# sch_LEDCUBE.net
KiCad netlist of a schematic drawn in Altium Designer
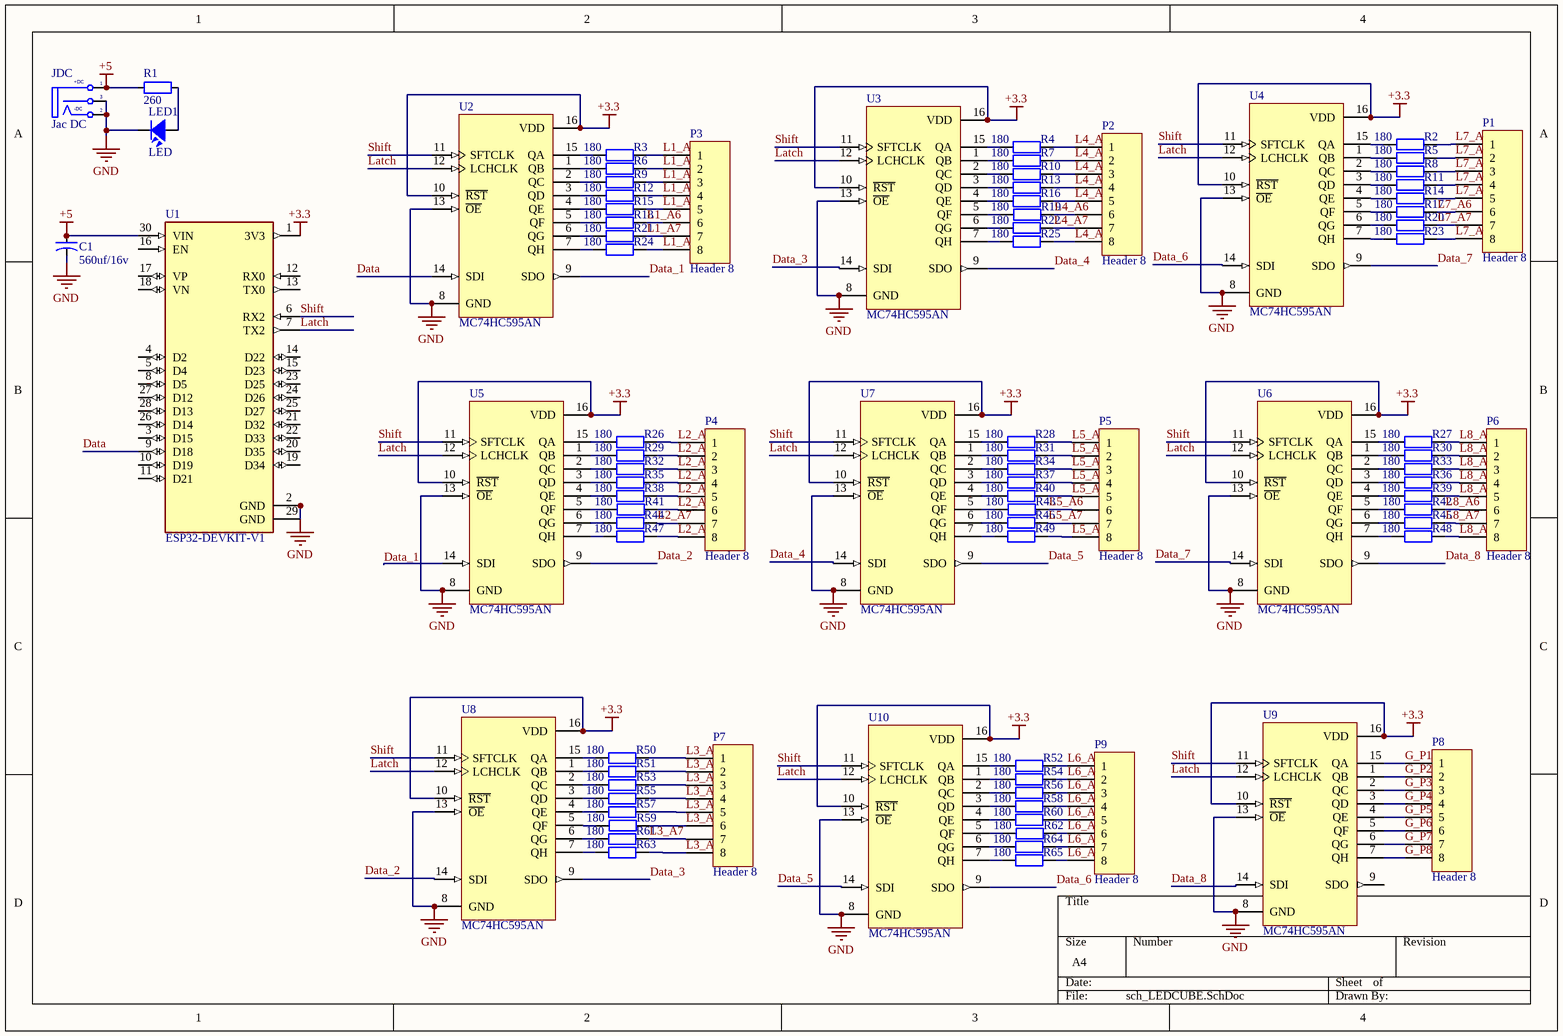
[diagram p0: sch_LEDCUBE.SchDoc]

(export (version "E")
  (design (tool "Eeschema 10.0.6"))
  (components
    (comp (ref "C1")
      (value "560uf/16v")
      (footprint "CA-ALU-8")
      (description "Capacitor (Semiconductor SIM Model)")
      (libsource (lib "My Library") (part "CAP-ALU-DIP"))
    )
    (comp (ref "JDC")
      (value "Jac DC")
      (footprint "DC-IN")
      (description "Jac DC input")
      (libsource (lib "My Library") (part "DCIN"))
    )
    (comp (ref "LED1")
      (value "LED")
      (footprint "LED-3")
      (description "LED Single colour Green and Red")
      (libsource (lib "My Library") (part "LED"))
    )
    (comp (ref "P1")
      (value "Header 8")
      (footprint "CON_8P")
      (description "Header, 8-Pin")
      (libsource (lib "My Library") (part "Header 8"))
    )
    (comp (ref "P2")
      (value "Header 8")
      (footprint "CON_8P")
      (description "Header, 8-Pin")
      (libsource (lib "My Library") (part "Header 8"))
    )
    (comp (ref "P3")
      (value "Header 8")
      (footprint "CON_8P")
      (description "Header, 8-Pin")
      (libsource (lib "My Library") (part "Header 8"))
    )
    (comp (ref "P4")
      (value "Header 8")
      (footprint "CON_8P")
      (description "Header, 8-Pin")
      (libsource (lib "My Library") (part "Header 8"))
    )
    (comp (ref "P5")
      (value "Header 8")
      (footprint "CON_8P")
      (description "Header, 8-Pin")
      (libsource (lib "My Library") (part "Header 8"))
    )
    (comp (ref "P6")
      (value "Header 8")
      (footprint "CON_8P")
      (description "Header, 8-Pin")
      (libsource (lib "My Library") (part "Header 8"))
    )
    (comp (ref "P7")
      (value "Header 8")
      (footprint "CON_8P")
      (description "Header, 8-Pin")
      (libsource (lib "My Library") (part "Header 8"))
    )
    (comp (ref "P8")
      (value "Header 8")
      (footprint "CON_8P")
      (description "Header, 8-Pin")
      (libsource (lib "My Library") (part "Header 8"))
    )
    (comp (ref "P9")
      (value "Header 8")
      (footprint "CON_8P")
      (description "Header, 8-Pin")
      (libsource (lib "My Library") (part "Header 8"))
    )
    (comp (ref "R1")
      (value "260")
      (footprint "RES-1/8W")
      (description "Resistor - DIP")
      (libsource (lib "My Library") (part "Resistor - DIP"))
    )
    (comp (ref "R2")
      (value "180")
      (footprint "RES-SMD-1206")
      (description "Resistor SMD")
      (fields (field (name "MANUFACTURER") "Generic Components"))
      (libsource (lib "My Library") (part "Resistor - SMD"))
    )
    (comp (ref "R3")
      (value "180")
      (footprint "RES-SMD-1206")
      (description "Resistor SMD")
      (fields (field (name "MANUFACTURER") "Generic Components"))
      (libsource (lib "My Library") (part "Resistor - SMD"))
    )
    (comp (ref "R4")
      (value "180")
      (footprint "RES-SMD-1206")
      (description "Resistor SMD")
      (fields (field (name "MANUFACTURER") "Generic Components"))
      (libsource (lib "My Library") (part "Resistor - SMD"))
    )
    (comp (ref "R5")
      (value "180")
      (footprint "RES-SMD-1206")
      (description "Resistor SMD")
      (fields (field (name "MANUFACTURER") "Generic Components"))
      (libsource (lib "My Library") (part "Resistor - SMD"))
    )
    (comp (ref "R6")
      (value "180")
      (footprint "RES-SMD-1206")
      (description "Resistor SMD")
      (fields (field (name "MANUFACTURER") "Generic Components"))
      (libsource (lib "My Library") (part "Resistor - SMD"))
    )
    (comp (ref "R7")
      (value "180")
      (footprint "RES-SMD-1206")
      (description "Resistor SMD")
      (fields (field (name "MANUFACTURER") "Generic Components"))
      (libsource (lib "My Library") (part "Resistor - SMD"))
    )
    (comp (ref "R8")
      (value "180")
      (footprint "RES-SMD-1206")
      (description "Resistor SMD")
      (fields (field (name "MANUFACTURER") "Generic Components"))
      (libsource (lib "My Library") (part "Resistor - SMD"))
    )
    (comp (ref "R9")
      (value "180")
      (footprint "RES-SMD-1206")
      (description "Resistor SMD")
      (fields (field (name "MANUFACTURER") "Generic Components"))
      (libsource (lib "My Library") (part "Resistor - SMD"))
    )
    (comp (ref "R10")
      (value "180")
      (footprint "RES-SMD-1206")
      (description "Resistor SMD")
      (fields (field (name "MANUFACTURER") "Generic Components"))
      (libsource (lib "My Library") (part "Resistor - SMD"))
    )
    (comp (ref "R11")
      (value "180")
      (footprint "RES-SMD-1206")
      (description "Resistor SMD")
      (fields (field (name "MANUFACTURER") "Generic Components"))
      (libsource (lib "My Library") (part "Resistor - SMD"))
    )
    (comp (ref "R12")
      (value "180")
      (footprint "RES-SMD-1206")
      (description "Resistor SMD")
      (fields (field (name "MANUFACTURER") "Generic Components"))
      (libsource (lib "My Library") (part "Resistor - SMD"))
    )
    (comp (ref "R13")
      (value "180")
      (footprint "RES-SMD-1206")
      (description "Resistor SMD")
      (fields (field (name "MANUFACTURER") "Generic Components"))
      (libsource (lib "My Library") (part "Resistor - SMD"))
    )
    (comp (ref "R14")
      (value "180")
      (footprint "RES-SMD-1206")
      (description "Resistor SMD")
      (fields (field (name "MANUFACTURER") "Generic Components"))
      (libsource (lib "My Library") (part "Resistor - SMD"))
    )
    (comp (ref "R15")
      (value "180")
      (footprint "RES-SMD-1206")
      (description "Resistor SMD")
      (fields (field (name "MANUFACTURER") "Generic Components"))
      (libsource (lib "My Library") (part "Resistor - SMD"))
    )
    (comp (ref "R16")
      (value "180")
      (footprint "RES-SMD-1206")
      (description "Resistor SMD")
      (fields (field (name "MANUFACTURER") "Generic Components"))
      (libsource (lib "My Library") (part "Resistor - SMD"))
    )
    (comp (ref "R17")
      (value "180")
      (footprint "RES-SMD-1206")
      (description "Resistor SMD")
      (fields (field (name "MANUFACTURER") "Generic Components"))
      (libsource (lib "My Library") (part "Resistor - SMD"))
    )
    (comp (ref "R18")
      (value "180")
      (footprint "RES-SMD-1206")
      (description "Resistor SMD")
      (fields (field (name "MANUFACTURER") "Generic Components"))
      (libsource (lib "My Library") (part "Resistor - SMD"))
    )
    (comp (ref "R19")
      (value "180")
      (footprint "RES-SMD-1206")
      (description "Resistor SMD")
      (fields (field (name "MANUFACTURER") "Generic Components"))
      (libsource (lib "My Library") (part "Resistor - SMD"))
    )
    (comp (ref "R20")
      (value "180")
      (footprint "RES-SMD-1206")
      (description "Resistor SMD")
      (fields (field (name "MANUFACTURER") "Generic Components"))
      (libsource (lib "My Library") (part "Resistor - SMD"))
    )
    (comp (ref "R21")
      (value "180")
      (footprint "RES-SMD-1206")
      (description "Resistor SMD")
      (fields (field (name "MANUFACTURER") "Generic Components"))
      (libsource (lib "My Library") (part "Resistor - SMD"))
    )
    (comp (ref "R22")
      (value "180")
      (footprint "RES-SMD-1206")
      (description "Resistor SMD")
      (fields (field (name "MANUFACTURER") "Generic Components"))
      (libsource (lib "My Library") (part "Resistor - SMD"))
    )
    (comp (ref "R23")
      (value "180")
      (footprint "RES-SMD-1206")
      (description "Resistor SMD")
      (fields (field (name "MANUFACTURER") "Generic Components"))
      (libsource (lib "My Library") (part "Resistor - SMD"))
    )
    (comp (ref "R24")
      (value "180")
      (footprint "RES-SMD-1206")
      (description "Resistor SMD")
      (fields (field (name "MANUFACTURER") "Generic Components"))
      (libsource (lib "My Library") (part "Resistor - SMD"))
    )
    (comp (ref "R25")
      (value "180")
      (footprint "RES-SMD-1206")
      (description "Resistor SMD")
      (fields (field (name "MANUFACTURER") "Generic Components"))
      (libsource (lib "My Library") (part "Resistor - SMD"))
    )
    (comp (ref "R26")
      (value "180")
      (footprint "RES-SMD-1206")
      (description "Resistor SMD")
      (fields (field (name "MANUFACTURER") "Generic Components"))
      (libsource (lib "My Library") (part "Resistor - SMD"))
    )
    (comp (ref "R27")
      (value "180")
      (footprint "RES-SMD-1206")
      (description "Resistor SMD")
      (fields (field (name "MANUFACTURER") "Generic Components"))
      (libsource (lib "My Library") (part "Resistor - SMD"))
    )
    (comp (ref "R28")
      (value "180")
      (footprint "RES-SMD-1206")
      (description "Resistor SMD")
      (fields (field (name "MANUFACTURER") "Generic Components"))
      (libsource (lib "My Library") (part "Resistor - SMD"))
    )
    (comp (ref "R29")
      (value "180")
      (footprint "RES-SMD-1206")
      (description "Resistor SMD")
      (fields (field (name "MANUFACTURER") "Generic Components"))
      (libsource (lib "My Library") (part "Resistor - SMD"))
    )
    (comp (ref "R30")
      (value "180")
      (footprint "RES-SMD-1206")
      (description "Resistor SMD")
      (fields (field (name "MANUFACTURER") "Generic Components"))
      (libsource (lib "My Library") (part "Resistor - SMD"))
    )
    (comp (ref "R31")
      (value "180")
      (footprint "RES-SMD-1206")
      (description "Resistor SMD")
      (fields (field (name "MANUFACTURER") "Generic Components"))
      (libsource (lib "My Library") (part "Resistor - SMD"))
    )
    (comp (ref "R32")
      (value "180")
      (footprint "RES-SMD-1206")
      (description "Resistor SMD")
      (fields (field (name "MANUFACTURER") "Generic Components"))
      (libsource (lib "My Library") (part "Resistor - SMD"))
    )
    (comp (ref "R33")
      (value "180")
      (footprint "RES-SMD-1206")
      (description "Resistor SMD")
      (fields (field (name "MANUFACTURER") "Generic Components"))
      (libsource (lib "My Library") (part "Resistor - SMD"))
    )
    (comp (ref "R34")
      (value "180")
      (footprint "RES-SMD-1206")
      (description "Resistor SMD")
      (fields (field (name "MANUFACTURER") "Generic Components"))
      (libsource (lib "My Library") (part "Resistor - SMD"))
    )
    (comp (ref "R35")
      (value "180")
      (footprint "RES-SMD-1206")
      (description "Resistor SMD")
      (fields (field (name "MANUFACTURER") "Generic Components"))
      (libsource (lib "My Library") (part "Resistor - SMD"))
    )
    (comp (ref "R36")
      (value "180")
      (footprint "RES-SMD-1206")
      (description "Resistor SMD")
      (fields (field (name "MANUFACTURER") "Generic Components"))
      (libsource (lib "My Library") (part "Resistor - SMD"))
    )
    (comp (ref "R37")
      (value "180")
      (footprint "RES-SMD-1206")
      (description "Resistor SMD")
      (fields (field (name "MANUFACTURER") "Generic Components"))
      (libsource (lib "My Library") (part "Resistor - SMD"))
    )
    (comp (ref "R38")
      (value "180")
      (footprint "RES-SMD-1206")
      (description "Resistor SMD")
      (fields (field (name "MANUFACTURER") "Generic Components"))
      (libsource (lib "My Library") (part "Resistor - SMD"))
    )
    (comp (ref "R39")
      (value "180")
      (footprint "RES-SMD-1206")
      (description "Resistor SMD")
      (fields (field (name "MANUFACTURER") "Generic Components"))
      (libsource (lib "My Library") (part "Resistor - SMD"))
    )
    (comp (ref "R40")
      (value "180")
      (footprint "RES-SMD-1206")
      (description "Resistor SMD")
      (fields (field (name "MANUFACTURER") "Generic Components"))
      (libsource (lib "My Library") (part "Resistor - SMD"))
    )
    (comp (ref "R41")
      (value "180")
      (footprint "RES-SMD-1206")
      (description "Resistor SMD")
      (fields (field (name "MANUFACTURER") "Generic Components"))
      (libsource (lib "My Library") (part "Resistor - SMD"))
    )
    (comp (ref "R42")
      (value "180")
      (footprint "RES-SMD-1206")
      (description "Resistor SMD")
      (fields (field (name "MANUFACTURER") "Generic Components"))
      (libsource (lib "My Library") (part "Resistor - SMD"))
    )
    (comp (ref "R43")
      (value "180")
      (footprint "RES-SMD-1206")
      (description "Resistor SMD")
      (fields (field (name "MANUFACTURER") "Generic Components"))
      (libsource (lib "My Library") (part "Resistor - SMD"))
    )
    (comp (ref "R44")
      (value "180")
      (footprint "RES-SMD-1206")
      (description "Resistor SMD")
      (fields (field (name "MANUFACTURER") "Generic Components"))
      (libsource (lib "My Library") (part "Resistor - SMD"))
    )
    (comp (ref "R45")
      (value "180")
      (footprint "RES-SMD-1206")
      (description "Resistor SMD")
      (fields (field (name "MANUFACTURER") "Generic Components"))
      (libsource (lib "My Library") (part "Resistor - SMD"))
    )
    (comp (ref "R46")
      (value "180")
      (footprint "RES-SMD-1206")
      (description "Resistor SMD")
      (fields (field (name "MANUFACTURER") "Generic Components"))
      (libsource (lib "My Library") (part "Resistor - SMD"))
    )
    (comp (ref "R47")
      (value "180")
      (footprint "RES-SMD-1206")
      (description "Resistor SMD")
      (fields (field (name "MANUFACTURER") "Generic Components"))
      (libsource (lib "My Library") (part "Resistor - SMD"))
    )
    (comp (ref "R48")
      (value "180")
      (footprint "RES-SMD-1206")
      (description "Resistor SMD")
      (fields (field (name "MANUFACTURER") "Generic Components"))
      (libsource (lib "My Library") (part "Resistor - SMD"))
    )
    (comp (ref "R49")
      (value "180")
      (footprint "RES-SMD-1206")
      (description "Resistor SMD")
      (fields (field (name "MANUFACTURER") "Generic Components"))
      (libsource (lib "My Library") (part "Resistor - SMD"))
    )
    (comp (ref "R50")
      (value "180")
      (footprint "RES-SMD-1206")
      (description "Resistor SMD")
      (fields (field (name "MANUFACTURER") "Generic Components"))
      (libsource (lib "My Library") (part "Resistor - SMD"))
    )
    (comp (ref "R51")
      (value "180")
      (footprint "RES-SMD-1206")
      (description "Resistor SMD")
      (fields (field (name "MANUFACTURER") "Generic Components"))
      (libsource (lib "My Library") (part "Resistor - SMD"))
    )
    (comp (ref "R52")
      (value "180")
      (footprint "RES-SMD-1206")
      (description "Resistor SMD")
      (fields (field (name "MANUFACTURER") "Generic Components"))
      (libsource (lib "My Library") (part "Resistor - SMD"))
    )
    (comp (ref "R53")
      (value "180")
      (footprint "RES-SMD-1206")
      (description "Resistor SMD")
      (fields (field (name "MANUFACTURER") "Generic Components"))
      (libsource (lib "My Library") (part "Resistor - SMD"))
    )
    (comp (ref "R54")
      (value "180")
      (footprint "RES-SMD-1206")
      (description "Resistor SMD")
      (fields (field (name "MANUFACTURER") "Generic Components"))
      (libsource (lib "My Library") (part "Resistor - SMD"))
    )
    (comp (ref "R55")
      (value "180")
      (footprint "RES-SMD-1206")
      (description "Resistor SMD")
      (fields (field (name "MANUFACTURER") "Generic Components"))
      (libsource (lib "My Library") (part "Resistor - SMD"))
    )
    (comp (ref "R56")
      (value "180")
      (footprint "RES-SMD-1206")
      (description "Resistor SMD")
      (fields (field (name "MANUFACTURER") "Generic Components"))
      (libsource (lib "My Library") (part "Resistor - SMD"))
    )
    (comp (ref "R57")
      (value "180")
      (footprint "RES-SMD-1206")
      (description "Resistor SMD")
      (fields (field (name "MANUFACTURER") "Generic Components"))
      (libsource (lib "My Library") (part "Resistor - SMD"))
    )
    (comp (ref "R58")
      (value "180")
      (footprint "RES-SMD-1206")
      (description "Resistor SMD")
      (fields (field (name "MANUFACTURER") "Generic Components"))
      (libsource (lib "My Library") (part "Resistor - SMD"))
    )
    (comp (ref "R59")
      (value "180")
      (footprint "RES-SMD-1206")
      (description "Resistor SMD")
      (fields (field (name "MANUFACTURER") "Generic Components"))
      (libsource (lib "My Library") (part "Resistor - SMD"))
    )
    (comp (ref "R60")
      (value "180")
      (footprint "RES-SMD-1206")
      (description "Resistor SMD")
      (fields (field (name "MANUFACTURER") "Generic Components"))
      (libsource (lib "My Library") (part "Resistor - SMD"))
    )
    (comp (ref "R61")
      (value "180")
      (footprint "RES-SMD-1206")
      (description "Resistor SMD")
      (fields (field (name "MANUFACTURER") "Generic Components"))
      (libsource (lib "My Library") (part "Resistor - SMD"))
    )
    (comp (ref "R62")
      (value "180")
      (footprint "RES-SMD-1206")
      (description "Resistor SMD")
      (fields (field (name "MANUFACTURER") "Generic Components"))
      (libsource (lib "My Library") (part "Resistor - SMD"))
    )
    (comp (ref "R63")
      (value "180")
      (footprint "RES-SMD-1206")
      (description "Resistor SMD")
      (fields (field (name "MANUFACTURER") "Generic Components"))
      (libsource (lib "My Library") (part "Resistor - SMD"))
    )
    (comp (ref "R64")
      (value "180")
      (footprint "RES-SMD-1206")
      (description "Resistor SMD")
      (fields (field (name "MANUFACTURER") "Generic Components"))
      (libsource (lib "My Library") (part "Resistor - SMD"))
    )
    (comp (ref "R65")
      (value "180")
      (footprint "RES-SMD-1206")
      (description "Resistor SMD")
      (fields (field (name "MANUFACTURER") "Generic Components"))
      (libsource (lib "My Library") (part "Resistor - SMD"))
    )
    (comp (ref "U1")
      (value "ESP32-DEVKIT-V1")
      (footprint "MODULE_ESP32_DEVKIT_V1")
      (libsource (lib "ESP32-DEVKIT-V1") (part "ESP32-DEVKIT-V1"))
    )
    (comp (ref "U2")
      (value "MC74HC595AN")
      (footprint "DIP.100/16/W.300/L.900")
      (description "8-Bit Serial-Input/Serial or Prallel-Output Shift Register with Latched 3-State Outputs")
      (libsource (lib "My Library") (part "MC74HC595AN"))
    )
    (comp (ref "U3")
      (value "MC74HC595AN")
      (footprint "DIP.100/16/W.300/L.900")
      (description "8-Bit Serial-Input/Serial or Prallel-Output Shift Register with Latched 3-State Outputs")
      (libsource (lib "My Library") (part "MC74HC595AN"))
    )
    (comp (ref "U4")
      (value "MC74HC595AN")
      (footprint "DIP.100/16/W.300/L.900")
      (description "8-Bit Serial-Input/Serial or Prallel-Output Shift Register with Latched 3-State Outputs")
      (libsource (lib "My Library") (part "MC74HC595AN"))
    )
    (comp (ref "U5")
      (value "MC74HC595AN")
      (footprint "DIP.100/16/W.300/L.900")
      (description "8-Bit Serial-Input/Serial or Prallel-Output Shift Register with Latched 3-State Outputs")
      (libsource (lib "My Library") (part "MC74HC595AN"))
    )
    (comp (ref "U6")
      (value "MC74HC595AN")
      (footprint "DIP.100/16/W.300/L.900")
      (description "8-Bit Serial-Input/Serial or Prallel-Output Shift Register with Latched 3-State Outputs")
      (libsource (lib "My Library") (part "MC74HC595AN"))
    )
    (comp (ref "U7")
      (value "MC74HC595AN")
      (footprint "DIP.100/16/W.300/L.900")
      (description "8-Bit Serial-Input/Serial or Prallel-Output Shift Register with Latched 3-State Outputs")
      (libsource (lib "My Library") (part "MC74HC595AN"))
    )
    (comp (ref "U8")
      (value "MC74HC595AN")
      (footprint "DIP.100/16/W.300/L.900")
      (description "8-Bit Serial-Input/Serial or Prallel-Output Shift Register with Latched 3-State Outputs")
      (libsource (lib "My Library") (part "MC74HC595AN"))
    )
    (comp (ref "U9")
      (value "MC74HC595AN")
      (footprint "DIP.100/16/W.300/L.900")
      (description "8-Bit Serial-Input/Serial or Prallel-Output Shift Register with Latched 3-State Outputs")
      (libsource (lib "My Library") (part "MC74HC595AN"))
    )
    (comp (ref "U10")
      (value "MC74HC595AN")
      (footprint "DIP.100/16/W.300/L.900")
      (description "8-Bit Serial-Input/Serial or Prallel-Output Shift Register with Latched 3-State Outputs")
      (libsource (lib "My Library") (part "MC74HC595AN"))
    )
  )
  (nets
    (net (code "1") (name "+3.3") (class "Default")
      (node (ref "U1") (pin "1") (pinfunction "3V3_1") (pintype "output"))
      (node (ref "U10") (pin "10") (pinfunction "~{RST}_10") (pintype "input"))
      (node (ref "U10") (pin "16") (pinfunction "VDD_16") (pintype "power_in"))
      (node (ref "U2") (pin "10") (pinfunction "~{RST}_10") (pintype "input"))
      (node (ref "U2") (pin "16") (pinfunction "VDD_16") (pintype "power_in"))
      (node (ref "U3") (pin "10") (pinfunction "~{RST}_10") (pintype "input"))
      (node (ref "U3") (pin "16") (pinfunction "VDD_16") (pintype "power_in"))
      (node (ref "U4") (pin "10") (pinfunction "~{RST}_10") (pintype "input"))
      (node (ref "U4") (pin "16") (pinfunction "VDD_16") (pintype "power_in"))
      (node (ref "U5") (pin "10") (pinfunction "~{RST}_10") (pintype "input"))
      (node (ref "U5") (pin "16") (pinfunction "VDD_16") (pintype "power_in"))
      (node (ref "U6") (pin "10") (pinfunction "~{RST}_10") (pintype "input"))
      (node (ref "U6") (pin "16") (pinfunction "VDD_16") (pintype "power_in"))
      (node (ref "U7") (pin "10") (pinfunction "~{RST}_10") (pintype "input"))
      (node (ref "U7") (pin "16") (pinfunction "VDD_16") (pintype "power_in"))
      (node (ref "U8") (pin "10") (pinfunction "~{RST}_10") (pintype "input"))
      (node (ref "U8") (pin "16") (pinfunction "VDD_16") (pintype "power_in"))
      (node (ref "U9") (pin "10") (pinfunction "~{RST}_10") (pintype "input"))
      (node (ref "U9") (pin "16") (pinfunction "VDD_16") (pintype "power_in"))
    )
    (net (code "2") (name "+5") (class "Default")
      (node (ref "C1") (pin "1") (pinfunction "1_1") (pintype "passive"))
      (node (ref "JDC") (pin "1") (pinfunction "T_1") (pintype "passive"))
      (node (ref "R1") (pin "2") (pinfunction "2_2") (pintype "passive"))
      (node (ref "U1") (pin "30") (pinfunction "VIN_30") (pintype "input"))
    )
    (net (code "3") (name "/Data") (class "Default")
      (node (ref "U1") (pin "9") (pinfunction "D18_9") (pintype "bidirectional"))
      (node (ref "U2") (pin "14") (pinfunction "SDI_14") (pintype "input"))
    )
    (net (code "4") (name "/Data_1") (class "Default")
      (node (ref "U2") (pin "9") (pinfunction "SDO_9") (pintype "output"))
      (node (ref "U5") (pin "14") (pinfunction "SDI_14") (pintype "input"))
    )
    (net (code "5") (name "/Data_2") (class "Default")
      (node (ref "U5") (pin "9") (pinfunction "SDO_9") (pintype "output"))
      (node (ref "U8") (pin "14") (pinfunction "SDI_14") (pintype "input"))
    )
    (net (code "6") (name "/Data_3") (class "Default")
      (node (ref "U3") (pin "14") (pinfunction "SDI_14") (pintype "input"))
      (node (ref "U8") (pin "9") (pinfunction "SDO_9") (pintype "output"))
    )
    (net (code "7") (name "/Data_4") (class "Default")
      (node (ref "U3") (pin "9") (pinfunction "SDO_9") (pintype "output"))
      (node (ref "U7") (pin "14") (pinfunction "SDI_14") (pintype "input"))
    )
    (net (code "8") (name "/Data_5") (class "Default")
      (node (ref "U10") (pin "14") (pinfunction "SDI_14") (pintype "input"))
      (node (ref "U7") (pin "9") (pinfunction "SDO_9") (pintype "output"))
    )
    (net (code "9") (name "/Data_6") (class "Default")
      (node (ref "U10") (pin "9") (pinfunction "SDO_9") (pintype "output"))
      (node (ref "U4") (pin "14") (pinfunction "SDI_14") (pintype "input"))
    )
    (net (code "10") (name "/Data_7") (class "Default")
      (node (ref "U4") (pin "9") (pinfunction "SDO_9") (pintype "output"))
      (node (ref "U6") (pin "14") (pinfunction "SDI_14") (pintype "input"))
    )
    (net (code "11") (name "/Data_8") (class "Default")
      (node (ref "U6") (pin "9") (pinfunction "SDO_9") (pintype "output"))
      (node (ref "U9") (pin "14") (pinfunction "SDI_14") (pintype "input"))
    )
    (net (code "12") (name "/G_P1") (class "Default")
      (node (ref "P8") (pin "1") (pinfunction "1_1") (pintype "passive"))
      (node (ref "U9") (pin "15") (pinfunction "QA_15") (pintype "tri_state"))
    )
    (net (code "13") (name "/G_P2") (class "Default")
      (node (ref "P8") (pin "2") (pinfunction "2_2") (pintype "passive"))
      (node (ref "U9") (pin "1") (pinfunction "QB_1") (pintype "tri_state"))
    )
    (net (code "14") (name "/G_P3") (class "Default")
      (node (ref "P8") (pin "3") (pinfunction "3_3") (pintype "passive"))
      (node (ref "U9") (pin "2") (pinfunction "QC_2") (pintype "tri_state"))
    )
    (net (code "15") (name "/G_P4") (class "Default")
      (node (ref "P8") (pin "4") (pinfunction "4_4") (pintype "passive"))
      (node (ref "U9") (pin "3") (pinfunction "QD_3") (pintype "tri_state"))
    )
    (net (code "16") (name "/G_P5") (class "Default")
      (node (ref "P8") (pin "5") (pinfunction "5_5") (pintype "passive"))
      (node (ref "U9") (pin "4") (pinfunction "QE_4") (pintype "tri_state"))
    )
    (net (code "17") (name "/G_P6") (class "Default")
      (node (ref "P8") (pin "6") (pinfunction "6_6") (pintype "passive"))
      (node (ref "U9") (pin "5") (pinfunction "QF_5") (pintype "tri_state"))
    )
    (net (code "18") (name "/G_P7") (class "Default")
      (node (ref "P8") (pin "7") (pinfunction "7_7") (pintype "passive"))
      (node (ref "U9") (pin "6") (pinfunction "QG_6") (pintype "tri_state"))
    )
    (net (code "19") (name "/G_P8") (class "Default")
      (node (ref "P8") (pin "8") (pinfunction "8_8") (pintype "passive"))
      (node (ref "U9") (pin "7") (pinfunction "QH_7") (pintype "tri_state"))
    )
    (net (code "20") (name "/L1_A1") (class "Default")
      (node (ref "P3") (pin "1") (pinfunction "1_1") (pintype "passive"))
      (node (ref "R3") (pin "1") (pinfunction "1_1") (pintype "passive"))
    )
    (net (code "21") (name "/L1_A2") (class "Default")
      (node (ref "P3") (pin "2") (pinfunction "2_2") (pintype "passive"))
      (node (ref "R6") (pin "1") (pinfunction "1_1") (pintype "passive"))
    )
    (net (code "22") (name "/L1_A3") (class "Default")
      (node (ref "P3") (pin "3") (pinfunction "3_3") (pintype "passive"))
      (node (ref "R9") (pin "1") (pinfunction "1_1") (pintype "passive"))
    )
    (net (code "23") (name "/L1_A4") (class "Default")
      (node (ref "P3") (pin "4") (pinfunction "4_4") (pintype "passive"))
      (node (ref "R12") (pin "1") (pinfunction "1_1") (pintype "passive"))
    )
    (net (code "24") (name "/L1_A5") (class "Default")
      (node (ref "P3") (pin "5") (pinfunction "5_5") (pintype "passive"))
      (node (ref "R15") (pin "1") (pinfunction "1_1") (pintype "passive"))
    )
    (net (code "25") (name "/L1_A6") (class "Default")
      (node (ref "P3") (pin "6") (pinfunction "6_6") (pintype "passive"))
      (node (ref "R18") (pin "1") (pinfunction "1_1") (pintype "passive"))
    )
    (net (code "26") (name "/L1_A7") (class "Default")
      (node (ref "P3") (pin "7") (pinfunction "7_7") (pintype "passive"))
      (node (ref "R21") (pin "1") (pinfunction "1_1") (pintype "passive"))
    )
    (net (code "27") (name "/L1_A8") (class "Default")
      (node (ref "P3") (pin "8") (pinfunction "8_8") (pintype "passive"))
      (node (ref "R24") (pin "1") (pinfunction "1_1") (pintype "passive"))
    )
    (net (code "28") (name "/L2_A1") (class "Default")
      (node (ref "P4") (pin "1") (pinfunction "1_1") (pintype "passive"))
      (node (ref "R26") (pin "1") (pinfunction "1_1") (pintype "passive"))
    )
    (net (code "29") (name "/L2_A2") (class "Default")
      (node (ref "P4") (pin "2") (pinfunction "2_2") (pintype "passive"))
      (node (ref "R29") (pin "1") (pinfunction "1_1") (pintype "passive"))
    )
    (net (code "30") (name "/L2_A3") (class "Default")
      (node (ref "P4") (pin "3") (pinfunction "3_3") (pintype "passive"))
      (node (ref "R32") (pin "1") (pinfunction "1_1") (pintype "passive"))
    )
    (net (code "31") (name "/L2_A4") (class "Default")
      (node (ref "P4") (pin "4") (pinfunction "4_4") (pintype "passive"))
      (node (ref "R35") (pin "1") (pinfunction "1_1") (pintype "passive"))
    )
    (net (code "32") (name "/L2_A5") (class "Default")
      (node (ref "P4") (pin "5") (pinfunction "5_5") (pintype "passive"))
      (node (ref "R38") (pin "1") (pinfunction "1_1") (pintype "passive"))
    )
    (net (code "33") (name "/L2_A6") (class "Default")
      (node (ref "P4") (pin "6") (pinfunction "6_6") (pintype "passive"))
      (node (ref "R41") (pin "1") (pinfunction "1_1") (pintype "passive"))
    )
    (net (code "34") (name "/L2_A7") (class "Default")
      (node (ref "P4") (pin "7") (pinfunction "7_7") (pintype "passive"))
      (node (ref "R44") (pin "1") (pinfunction "1_1") (pintype "passive"))
    )
    (net (code "35") (name "/L2_A8") (class "Default")
      (node (ref "P4") (pin "8") (pinfunction "8_8") (pintype "passive"))
      (node (ref "R47") (pin "1") (pinfunction "1_1") (pintype "passive"))
    )
    (net (code "36") (name "/L3_A1") (class "Default")
      (node (ref "P7") (pin "1") (pinfunction "1_1") (pintype "passive"))
      (node (ref "R50") (pin "1") (pinfunction "1_1") (pintype "passive"))
    )
    (net (code "37") (name "/L3_A2") (class "Default")
      (node (ref "P7") (pin "2") (pinfunction "2_2") (pintype "passive"))
      (node (ref "R51") (pin "1") (pinfunction "1_1") (pintype "passive"))
    )
    (net (code "38") (name "/L3_A3") (class "Default")
      (node (ref "P7") (pin "3") (pinfunction "3_3") (pintype "passive"))
      (node (ref "R53") (pin "1") (pinfunction "1_1") (pintype "passive"))
    )
    (net (code "39") (name "/L3_A4") (class "Default")
      (node (ref "P7") (pin "4") (pinfunction "4_4") (pintype "passive"))
      (node (ref "R55") (pin "1") (pinfunction "1_1") (pintype "passive"))
    )
    (net (code "40") (name "/L3_A5") (class "Default")
      (node (ref "P7") (pin "5") (pinfunction "5_5") (pintype "passive"))
      (node (ref "R57") (pin "1") (pinfunction "1_1") (pintype "passive"))
    )
    (net (code "41") (name "/L3_A6") (class "Default")
      (node (ref "P7") (pin "6") (pinfunction "6_6") (pintype "passive"))
      (node (ref "R59") (pin "1") (pinfunction "1_1") (pintype "passive"))
    )
    (net (code "42") (name "/L3_A7") (class "Default")
      (node (ref "P7") (pin "7") (pinfunction "7_7") (pintype "passive"))
      (node (ref "R61") (pin "1") (pinfunction "1_1") (pintype "passive"))
    )
    (net (code "43") (name "/L3_A8") (class "Default")
      (node (ref "P7") (pin "8") (pinfunction "8_8") (pintype "passive"))
      (node (ref "R63") (pin "1") (pinfunction "1_1") (pintype "passive"))
    )
    (net (code "44") (name "/L4_A1") (class "Default")
      (node (ref "P2") (pin "1") (pinfunction "1_1") (pintype "passive"))
      (node (ref "R4") (pin "1") (pinfunction "1_1") (pintype "passive"))
    )
    (net (code "45") (name "/L4_A2") (class "Default")
      (node (ref "P2") (pin "2") (pinfunction "2_2") (pintype "passive"))
      (node (ref "R7") (pin "1") (pinfunction "1_1") (pintype "passive"))
    )
    (net (code "46") (name "/L4_A3") (class "Default")
      (node (ref "P2") (pin "3") (pinfunction "3_3") (pintype "passive"))
      (node (ref "R10") (pin "1") (pinfunction "1_1") (pintype "passive"))
    )
    (net (code "47") (name "/L4_A4") (class "Default")
      (node (ref "P2") (pin "4") (pinfunction "4_4") (pintype "passive"))
      (node (ref "R13") (pin "1") (pinfunction "1_1") (pintype "passive"))
    )
    (net (code "48") (name "/L4_A5") (class "Default")
      (node (ref "P2") (pin "5") (pinfunction "5_5") (pintype "passive"))
      (node (ref "R16") (pin "1") (pinfunction "1_1") (pintype "passive"))
    )
    (net (code "49") (name "/L4_A6") (class "Default")
      (node (ref "P2") (pin "6") (pinfunction "6_6") (pintype "passive"))
      (node (ref "R19") (pin "1") (pinfunction "1_1") (pintype "passive"))
    )
    (net (code "50") (name "/L4_A7") (class "Default")
      (node (ref "P2") (pin "7") (pinfunction "7_7") (pintype "passive"))
      (node (ref "R22") (pin "1") (pinfunction "1_1") (pintype "passive"))
    )
    (net (code "51") (name "/L4_A8") (class "Default")
      (node (ref "P2") (pin "8") (pinfunction "8_8") (pintype "passive"))
      (node (ref "R25") (pin "1") (pinfunction "1_1") (pintype "passive"))
    )
    (net (code "52") (name "/L5_A1") (class "Default")
      (node (ref "P5") (pin "1") (pinfunction "1_1") (pintype "passive"))
      (node (ref "R28") (pin "1") (pinfunction "1_1") (pintype "passive"))
    )
    (net (code "53") (name "/L5_A2") (class "Default")
      (node (ref "P5") (pin "2") (pinfunction "2_2") (pintype "passive"))
      (node (ref "R31") (pin "1") (pinfunction "1_1") (pintype "passive"))
    )
    (net (code "54") (name "/L5_A3") (class "Default")
      (node (ref "P5") (pin "3") (pinfunction "3_3") (pintype "passive"))
      (node (ref "R34") (pin "1") (pinfunction "1_1") (pintype "passive"))
    )
    (net (code "55") (name "/L5_A4") (class "Default")
      (node (ref "P5") (pin "4") (pinfunction "4_4") (pintype "passive"))
      (node (ref "R37") (pin "1") (pinfunction "1_1") (pintype "passive"))
    )
    (net (code "56") (name "/L5_A5") (class "Default")
      (node (ref "P5") (pin "5") (pinfunction "5_5") (pintype "passive"))
      (node (ref "R40") (pin "1") (pinfunction "1_1") (pintype "passive"))
    )
    (net (code "57") (name "/L5_A6") (class "Default")
      (node (ref "P5") (pin "6") (pinfunction "6_6") (pintype "passive"))
      (node (ref "R43") (pin "1") (pinfunction "1_1") (pintype "passive"))
    )
    (net (code "58") (name "/L5_A7") (class "Default")
      (node (ref "P5") (pin "7") (pinfunction "7_7") (pintype "passive"))
      (node (ref "R46") (pin "1") (pinfunction "1_1") (pintype "passive"))
    )
    (net (code "59") (name "/L5_A8") (class "Default")
      (node (ref "P5") (pin "8") (pinfunction "8_8") (pintype "passive"))
      (node (ref "R49") (pin "1") (pinfunction "1_1") (pintype "passive"))
    )
    (net (code "60") (name "/L6_A1") (class "Default")
      (node (ref "P9") (pin "1") (pinfunction "1_1") (pintype "passive"))
      (node (ref "R52") (pin "1") (pinfunction "1_1") (pintype "passive"))
    )
    (net (code "61") (name "/L6_A2") (class "Default")
      (node (ref "P9") (pin "2") (pinfunction "2_2") (pintype "passive"))
      (node (ref "R54") (pin "1") (pinfunction "1_1") (pintype "passive"))
    )
    (net (code "62") (name "/L6_A3") (class "Default")
      (node (ref "P9") (pin "3") (pinfunction "3_3") (pintype "passive"))
      (node (ref "R56") (pin "1") (pinfunction "1_1") (pintype "passive"))
    )
    (net (code "63") (name "/L6_A4") (class "Default")
      (node (ref "P9") (pin "4") (pinfunction "4_4") (pintype "passive"))
      (node (ref "R58") (pin "1") (pinfunction "1_1") (pintype "passive"))
    )
    (net (code "64") (name "/L6_A5") (class "Default")
      (node (ref "P9") (pin "5") (pinfunction "5_5") (pintype "passive"))
      (node (ref "R60") (pin "1") (pinfunction "1_1") (pintype "passive"))
    )
    (net (code "67") (name "/L6_A6") (class "Default")
      (node (ref "P9") (pin "6") (pinfunction "6_6") (pintype "passive"))
      (node (ref "R62") (pin "1") (pinfunction "1_1") (pintype "passive"))
    )
    (net (code "68") (name "/L6_A7") (class "Default")
      (node (ref "P9") (pin "7") (pinfunction "7_7") (pintype "passive"))
      (node (ref "R64") (pin "1") (pinfunction "1_1") (pintype "passive"))
    )
    (net (code "69") (name "/L6_A8") (class "Default")
      (node (ref "P9") (pin "8") (pinfunction "8_8") (pintype "passive"))
      (node (ref "R65") (pin "1") (pinfunction "1_1") (pintype "passive"))
    )
    (net (code "70") (name "/L7_A1") (class "Default")
      (node (ref "P1") (pin "1") (pinfunction "1_1") (pintype "passive"))
      (node (ref "R2") (pin "1") (pinfunction "1_1") (pintype "passive"))
    )
    (net (code "71") (name "/L7_A2") (class "Default")
      (node (ref "P1") (pin "2") (pinfunction "2_2") (pintype "passive"))
      (node (ref "R5") (pin "1") (pinfunction "1_1") (pintype "passive"))
    )
    (net (code "72") (name "/L7_A3") (class "Default")
      (node (ref "P1") (pin "3") (pinfunction "3_3") (pintype "passive"))
      (node (ref "R8") (pin "1") (pinfunction "1_1") (pintype "passive"))
    )
    (net (code "73") (name "/L7_A4") (class "Default")
      (node (ref "P1") (pin "4") (pinfunction "4_4") (pintype "passive"))
      (node (ref "R11") (pin "1") (pinfunction "1_1") (pintype "passive"))
    )
    (net (code "74") (name "/L7_A5") (class "Default")
      (node (ref "P1") (pin "5") (pinfunction "5_5") (pintype "passive"))
      (node (ref "R14") (pin "1") (pinfunction "1_1") (pintype "passive"))
    )
    (net (code "75") (name "/L7_A6") (class "Default")
      (node (ref "P1") (pin "6") (pinfunction "6_6") (pintype "passive"))
      (node (ref "R17") (pin "1") (pinfunction "1_1") (pintype "passive"))
    )
    (net (code "76") (name "/L7_A7") (class "Default")
      (node (ref "P1") (pin "7") (pinfunction "7_7") (pintype "passive"))
      (node (ref "R20") (pin "1") (pinfunction "1_1") (pintype "passive"))
    )
    (net (code "77") (name "/L7_A8") (class "Default")
      (node (ref "P1") (pin "8") (pinfunction "8_8") (pintype "passive"))
      (node (ref "R23") (pin "1") (pinfunction "1_1") (pintype "passive"))
    )
    (net (code "78") (name "/L8_A1") (class "Default")
      (node (ref "P6") (pin "1") (pinfunction "1_1") (pintype "passive"))
      (node (ref "R27") (pin "1") (pinfunction "1_1") (pintype "passive"))
    )
    (net (code "79") (name "/L8_A2") (class "Default")
      (node (ref "P6") (pin "2") (pinfunction "2_2") (pintype "passive"))
      (node (ref "R30") (pin "1") (pinfunction "1_1") (pintype "passive"))
    )
    (net (code "80") (name "/L8_A3") (class "Default")
      (node (ref "P6") (pin "3") (pinfunction "3_3") (pintype "passive"))
      (node (ref "R33") (pin "1") (pinfunction "1_1") (pintype "passive"))
    )
    (net (code "81") (name "/L8_A4") (class "Default")
      (node (ref "P6") (pin "4") (pinfunction "4_4") (pintype "passive"))
      (node (ref "R36") (pin "1") (pinfunction "1_1") (pintype "passive"))
    )
    (net (code "82") (name "/L8_A5") (class "Default")
      (node (ref "P6") (pin "5") (pinfunction "5_5") (pintype "passive"))
      (node (ref "R39") (pin "1") (pinfunction "1_1") (pintype "passive"))
    )
    (net (code "83") (name "/L8_A6") (class "Default")
      (node (ref "P6") (pin "6") (pinfunction "6_6") (pintype "passive"))
      (node (ref "R42") (pin "1") (pinfunction "1_1") (pintype "passive"))
    )
    (net (code "84") (name "/L8_A7") (class "Default")
      (node (ref "P6") (pin "7") (pinfunction "7_7") (pintype "passive"))
      (node (ref "R45") (pin "1") (pinfunction "1_1") (pintype "passive"))
    )
    (net (code "85") (name "/L8_A8") (class "Default")
      (node (ref "P6") (pin "8") (pinfunction "8_8") (pintype "passive"))
      (node (ref "R48") (pin "1") (pinfunction "1_1") (pintype "passive"))
    )
    (net (code "86") (name "/Latch") (class "Default")
      (node (ref "U1") (pin "7") (pinfunction "TX2_7") (pintype "output"))
      (node (ref "U10") (pin "12") (pinfunction "LCHCLK_12") (pintype "input"))
      (node (ref "U2") (pin "12") (pinfunction "LCHCLK_12") (pintype "input"))
      (node (ref "U3") (pin "12") (pinfunction "LCHCLK_12") (pintype "input"))
      (node (ref "U4") (pin "12") (pinfunction "LCHCLK_12") (pintype "input"))
      (node (ref "U5") (pin "12") (pinfunction "LCHCLK_12") (pintype "input"))
      (node (ref "U6") (pin "12") (pinfunction "LCHCLK_12") (pintype "input"))
      (node (ref "U7") (pin "12") (pinfunction "LCHCLK_12") (pintype "input"))
      (node (ref "U8") (pin "12") (pinfunction "LCHCLK_12") (pintype "input"))
      (node (ref "U9") (pin "12") (pinfunction "LCHCLK_12") (pintype "input"))
    )
    (net (code "87") (name "/Shift") (class "Default")
      (node (ref "U1") (pin "6") (pinfunction "RX2_6") (pintype "input"))
      (node (ref "U10") (pin "11") (pinfunction "SFTCLK_11") (pintype "input"))
      (node (ref "U2") (pin "11") (pinfunction "SFTCLK_11") (pintype "input"))
      (node (ref "U3") (pin "11") (pinfunction "SFTCLK_11") (pintype "input"))
      (node (ref "U4") (pin "11") (pinfunction "SFTCLK_11") (pintype "input"))
      (node (ref "U5") (pin "11") (pinfunction "SFTCLK_11") (pintype "input"))
      (node (ref "U6") (pin "11") (pinfunction "SFTCLK_11") (pintype "input"))
      (node (ref "U7") (pin "11") (pinfunction "SFTCLK_11") (pintype "input"))
      (node (ref "U8") (pin "11") (pinfunction "SFTCLK_11") (pintype "input"))
      (node (ref "U9") (pin "11") (pinfunction "SFTCLK_11") (pintype "input"))
    )
    (net (code "88") (name "GND") (class "Default")
      (node (ref "C1") (pin "2") (pinfunction "2_2") (pintype "passive"))
      (node (ref "JDC") (pin "2") (pinfunction "TN_2") (pintype "passive"))
      (node (ref "JDC") (pin "3") (pinfunction "S_3") (pintype "power_in"))
      (node (ref "LED1") (pin "2") (pinfunction "2_2") (pintype "passive"))
      (node (ref "U1") (pin "2") (pinfunction "GND_2") (pintype "power_in"))
      (node (ref "U1") (pin "29") (pinfunction "GND_29") (pintype "power_in"))
      (node (ref "U10") (pin "13") (pinfunction "~{OE}_13") (pintype "input"))
      (node (ref "U10") (pin "8") (pinfunction "GND_8") (pintype "power_in"))
      (node (ref "U2") (pin "13") (pinfunction "~{OE}_13") (pintype "input"))
      (node (ref "U2") (pin "8") (pinfunction "GND_8") (pintype "power_in"))
      (node (ref "U3") (pin "13") (pinfunction "~{OE}_13") (pintype "input"))
      (node (ref "U3") (pin "8") (pinfunction "GND_8") (pintype "power_in"))
      (node (ref "U4") (pin "13") (pinfunction "~{OE}_13") (pintype "input"))
      (node (ref "U4") (pin "8") (pinfunction "GND_8") (pintype "power_in"))
      (node (ref "U5") (pin "13") (pinfunction "~{OE}_13") (pintype "input"))
      (node (ref "U5") (pin "8") (pinfunction "GND_8") (pintype "power_in"))
      (node (ref "U6") (pin "13") (pinfunction "~{OE}_13") (pintype "input"))
      (node (ref "U6") (pin "8") (pinfunction "GND_8") (pintype "power_in"))
      (node (ref "U7") (pin "13") (pinfunction "~{OE}_13") (pintype "input"))
      (node (ref "U7") (pin "8") (pinfunction "GND_8") (pintype "power_in"))
      (node (ref "U8") (pin "13") (pinfunction "~{OE}_13") (pintype "input"))
      (node (ref "U8") (pin "8") (pinfunction "GND_8") (pintype "power_in"))
      (node (ref "U9") (pin "13") (pinfunction "~{OE}_13") (pintype "input"))
      (node (ref "U9") (pin "8") (pinfunction "GND_8") (pintype "power_in"))
    )
    (net (code "89") (name "Net-(LED1-Pad1)") (class "Default")
      (node (ref "LED1") (pin "1") (pinfunction "1_1") (pintype "passive"))
      (node (ref "R1") (pin "1") (pinfunction "1_1") (pintype "passive"))
    )
    (net (code "90") (name "Net-(U2-QA)") (class "Default")
      (node (ref "R3") (pin "2") (pinfunction "2_2") (pintype "passive"))
      (node (ref "U2") (pin "15") (pinfunction "QA_15") (pintype "tri_state"))
    )
    (net (code "91") (name "Net-(U2-QB)") (class "Default")
      (node (ref "R6") (pin "2") (pinfunction "2_2") (pintype "passive"))
      (node (ref "U2") (pin "1") (pinfunction "QB_1") (pintype "tri_state"))
    )
    (net (code "92") (name "Net-(U2-QC)") (class "Default")
      (node (ref "R9") (pin "2") (pinfunction "2_2") (pintype "passive"))
      (node (ref "U2") (pin "2") (pinfunction "QC_2") (pintype "tri_state"))
    )
    (net (code "93") (name "Net-(U2-QD)") (class "Default")
      (node (ref "R12") (pin "2") (pinfunction "2_2") (pintype "passive"))
      (node (ref "U2") (pin "3") (pinfunction "QD_3") (pintype "tri_state"))
    )
    (net (code "94") (name "Net-(U2-QE)") (class "Default")
      (node (ref "R15") (pin "2") (pinfunction "2_2") (pintype "passive"))
      (node (ref "U2") (pin "4") (pinfunction "QE_4") (pintype "tri_state"))
    )
    (net (code "95") (name "Net-(U2-QF)") (class "Default")
      (node (ref "R18") (pin "2") (pinfunction "2_2") (pintype "passive"))
      (node (ref "U2") (pin "5") (pinfunction "QF_5") (pintype "tri_state"))
    )
    (net (code "96") (name "Net-(U2-QG)") (class "Default")
      (node (ref "R21") (pin "2") (pinfunction "2_2") (pintype "passive"))
      (node (ref "U2") (pin "6") (pinfunction "QG_6") (pintype "tri_state"))
    )
    (net (code "97") (name "Net-(U2-QH)") (class "Default")
      (node (ref "R24") (pin "2") (pinfunction "2_2") (pintype "passive"))
      (node (ref "U2") (pin "7") (pinfunction "QH_7") (pintype "tri_state"))
    )
    (net (code "98") (name "Net-(U3-QA)") (class "Default")
      (node (ref "R4") (pin "2") (pinfunction "2_2") (pintype "passive"))
      (node (ref "U3") (pin "15") (pinfunction "QA_15") (pintype "tri_state"))
    )
    (net (code "99") (name "Net-(U3-QB)") (class "Default")
      (node (ref "R7") (pin "2") (pinfunction "2_2") (pintype "passive"))
      (node (ref "U3") (pin "1") (pinfunction "QB_1") (pintype "tri_state"))
    )
    (net (code "100") (name "Net-(U3-QC)") (class "Default")
      (node (ref "R10") (pin "2") (pinfunction "2_2") (pintype "passive"))
      (node (ref "U3") (pin "2") (pinfunction "QC_2") (pintype "tri_state"))
    )
    (net (code "101") (name "Net-(U3-QD)") (class "Default")
      (node (ref "R13") (pin "2") (pinfunction "2_2") (pintype "passive"))
      (node (ref "U3") (pin "3") (pinfunction "QD_3") (pintype "tri_state"))
    )
    (net (code "102") (name "Net-(U3-QE)") (class "Default")
      (node (ref "R16") (pin "2") (pinfunction "2_2") (pintype "passive"))
      (node (ref "U3") (pin "4") (pinfunction "QE_4") (pintype "tri_state"))
    )
    (net (code "103") (name "Net-(U3-QF)") (class "Default")
      (node (ref "R19") (pin "2") (pinfunction "2_2") (pintype "passive"))
      (node (ref "U3") (pin "5") (pinfunction "QF_5") (pintype "tri_state"))
    )
    (net (code "104") (name "Net-(U3-QG)") (class "Default")
      (node (ref "R22") (pin "2") (pinfunction "2_2") (pintype "passive"))
      (node (ref "U3") (pin "6") (pinfunction "QG_6") (pintype "tri_state"))
    )
    (net (code "105") (name "Net-(U3-QH)") (class "Default")
      (node (ref "R25") (pin "2") (pinfunction "2_2") (pintype "passive"))
      (node (ref "U3") (pin "7") (pinfunction "QH_7") (pintype "tri_state"))
    )
    (net (code "106") (name "Net-(U4-QA)") (class "Default")
      (node (ref "R2") (pin "2") (pinfunction "2_2") (pintype "passive"))
      (node (ref "U4") (pin "15") (pinfunction "QA_15") (pintype "tri_state"))
    )
    (net (code "107") (name "Net-(U4-QB)") (class "Default")
      (node (ref "R5") (pin "2") (pinfunction "2_2") (pintype "passive"))
      (node (ref "U4") (pin "1") (pinfunction "QB_1") (pintype "tri_state"))
    )
    (net (code "108") (name "Net-(U4-QC)") (class "Default")
      (node (ref "R8") (pin "2") (pinfunction "2_2") (pintype "passive"))
      (node (ref "U4") (pin "2") (pinfunction "QC_2") (pintype "tri_state"))
    )
    (net (code "109") (name "Net-(U4-QD)") (class "Default")
      (node (ref "R11") (pin "2") (pinfunction "2_2") (pintype "passive"))
      (node (ref "U4") (pin "3") (pinfunction "QD_3") (pintype "tri_state"))
    )
    (net (code "110") (name "Net-(U4-QE)") (class "Default")
      (node (ref "R14") (pin "2") (pinfunction "2_2") (pintype "passive"))
      (node (ref "U4") (pin "4") (pinfunction "QE_4") (pintype "tri_state"))
    )
    (net (code "111") (name "Net-(U4-QF)") (class "Default")
      (node (ref "R17") (pin "2") (pinfunction "2_2") (pintype "passive"))
      (node (ref "U4") (pin "5") (pinfunction "QF_5") (pintype "tri_state"))
    )
    (net (code "112") (name "Net-(U4-QG)") (class "Default")
      (node (ref "R20") (pin "2") (pinfunction "2_2") (pintype "passive"))
      (node (ref "U4") (pin "6") (pinfunction "QG_6") (pintype "tri_state"))
    )
    (net (code "113") (name "Net-(U4-QH)") (class "Default")
      (node (ref "R23") (pin "2") (pinfunction "2_2") (pintype "passive"))
      (node (ref "U4") (pin "7") (pinfunction "QH_7") (pintype "tri_state"))
    )
    (net (code "114") (name "Net-(U5-QA)") (class "Default")
      (node (ref "R26") (pin "2") (pinfunction "2_2") (pintype "passive"))
      (node (ref "U5") (pin "15") (pinfunction "QA_15") (pintype "tri_state"))
    )
    (net (code "115") (name "Net-(U5-QB)") (class "Default")
      (node (ref "R29") (pin "2") (pinfunction "2_2") (pintype "passive"))
      (node (ref "U5") (pin "1") (pinfunction "QB_1") (pintype "tri_state"))
    )
    (net (code "116") (name "Net-(U5-QC)") (class "Default")
      (node (ref "R32") (pin "2") (pinfunction "2_2") (pintype "passive"))
      (node (ref "U5") (pin "2") (pinfunction "QC_2") (pintype "tri_state"))
    )
    (net (code "117") (name "Net-(U5-QD)") (class "Default")
      (node (ref "R35") (pin "2") (pinfunction "2_2") (pintype "passive"))
      (node (ref "U5") (pin "3") (pinfunction "QD_3") (pintype "tri_state"))
    )
    (net (code "118") (name "Net-(U5-QE)") (class "Default")
      (node (ref "R38") (pin "2") (pinfunction "2_2") (pintype "passive"))
      (node (ref "U5") (pin "4") (pinfunction "QE_4") (pintype "tri_state"))
    )
    (net (code "119") (name "Net-(U5-QF)") (class "Default")
      (node (ref "R41") (pin "2") (pinfunction "2_2") (pintype "passive"))
      (node (ref "U5") (pin "5") (pinfunction "QF_5") (pintype "tri_state"))
    )
    (net (code "120") (name "Net-(U5-QG)") (class "Default")
      (node (ref "R44") (pin "2") (pinfunction "2_2") (pintype "passive"))
      (node (ref "U5") (pin "6") (pinfunction "QG_6") (pintype "tri_state"))
    )
    (net (code "121") (name "Net-(U5-QH)") (class "Default")
      (node (ref "R47") (pin "2") (pinfunction "2_2") (pintype "passive"))
      (node (ref "U5") (pin "7") (pinfunction "QH_7") (pintype "tri_state"))
    )
    (net (code "122") (name "Net-(U6-QA)") (class "Default")
      (node (ref "R27") (pin "2") (pinfunction "2_2") (pintype "passive"))
      (node (ref "U6") (pin "15") (pinfunction "QA_15") (pintype "tri_state"))
    )
    (net (code "123") (name "Net-(U6-QB)") (class "Default")
      (node (ref "R30") (pin "2") (pinfunction "2_2") (pintype "passive"))
      (node (ref "U6") (pin "1") (pinfunction "QB_1") (pintype "tri_state"))
    )
    (net (code "124") (name "Net-(U6-QC)") (class "Default")
      (node (ref "R33") (pin "2") (pinfunction "2_2") (pintype "passive"))
      (node (ref "U6") (pin "2") (pinfunction "QC_2") (pintype "tri_state"))
    )
    (net (code "125") (name "Net-(U6-QD)") (class "Default")
      (node (ref "R36") (pin "2") (pinfunction "2_2") (pintype "passive"))
      (node (ref "U6") (pin "3") (pinfunction "QD_3") (pintype "tri_state"))
    )
    (net (code "126") (name "Net-(U6-QE)") (class "Default")
      (node (ref "R39") (pin "2") (pinfunction "2_2") (pintype "passive"))
      (node (ref "U6") (pin "4") (pinfunction "QE_4") (pintype "tri_state"))
    )
    (net (code "127") (name "Net-(U6-QF)") (class "Default")
      (node (ref "R42") (pin "2") (pinfunction "2_2") (pintype "passive"))
      (node (ref "U6") (pin "5") (pinfunction "QF_5") (pintype "tri_state"))
    )
    (net (code "128") (name "Net-(U6-QG)") (class "Default")
      (node (ref "R45") (pin "2") (pinfunction "2_2") (pintype "passive"))
      (node (ref "U6") (pin "6") (pinfunction "QG_6") (pintype "tri_state"))
    )
    (net (code "129") (name "Net-(U6-QH)") (class "Default")
      (node (ref "R48") (pin "2") (pinfunction "2_2") (pintype "passive"))
      (node (ref "U6") (pin "7") (pinfunction "QH_7") (pintype "tri_state"))
    )
    (net (code "130") (name "Net-(U7-QA)") (class "Default")
      (node (ref "R28") (pin "2") (pinfunction "2_2") (pintype "passive"))
      (node (ref "U7") (pin "15") (pinfunction "QA_15") (pintype "tri_state"))
    )
    (net (code "131") (name "Net-(U7-QB)") (class "Default")
      (node (ref "R31") (pin "2") (pinfunction "2_2") (pintype "passive"))
      (node (ref "U7") (pin "1") (pinfunction "QB_1") (pintype "tri_state"))
    )
    (net (code "132") (name "Net-(U7-QC)") (class "Default")
      (node (ref "R34") (pin "2") (pinfunction "2_2") (pintype "passive"))
      (node (ref "U7") (pin "2") (pinfunction "QC_2") (pintype "tri_state"))
    )
    (net (code "133") (name "Net-(U7-QD)") (class "Default")
      (node (ref "R37") (pin "2") (pinfunction "2_2") (pintype "passive"))
      (node (ref "U7") (pin "3") (pinfunction "QD_3") (pintype "tri_state"))
    )
    (net (code "134") (name "Net-(U7-QE)") (class "Default")
      (node (ref "R40") (pin "2") (pinfunction "2_2") (pintype "passive"))
      (node (ref "U7") (pin "4") (pinfunction "QE_4") (pintype "tri_state"))
    )
    (net (code "135") (name "Net-(U7-QF)") (class "Default")
      (node (ref "R43") (pin "2") (pinfunction "2_2") (pintype "passive"))
      (node (ref "U7") (pin "5") (pinfunction "QF_5") (pintype "tri_state"))
    )
    (net (code "136") (name "Net-(U7-QG)") (class "Default")
      (node (ref "R46") (pin "2") (pinfunction "2_2") (pintype "passive"))
      (node (ref "U7") (pin "6") (pinfunction "QG_6") (pintype "tri_state"))
    )
    (net (code "137") (name "Net-(U7-QH)") (class "Default")
      (node (ref "R49") (pin "2") (pinfunction "2_2") (pintype "passive"))
      (node (ref "U7") (pin "7") (pinfunction "QH_7") (pintype "tri_state"))
    )
    (net (code "138") (name "Net-(U8-QA)") (class "Default")
      (node (ref "R50") (pin "2") (pinfunction "2_2") (pintype "passive"))
      (node (ref "U8") (pin "15") (pinfunction "QA_15") (pintype "tri_state"))
    )
    (net (code "139") (name "Net-(U8-QB)") (class "Default")
      (node (ref "R51") (pin "2") (pinfunction "2_2") (pintype "passive"))
      (node (ref "U8") (pin "1") (pinfunction "QB_1") (pintype "tri_state"))
    )
    (net (code "140") (name "Net-(U8-QC)") (class "Default")
      (node (ref "R53") (pin "2") (pinfunction "2_2") (pintype "passive"))
      (node (ref "U8") (pin "2") (pinfunction "QC_2") (pintype "tri_state"))
    )
    (net (code "141") (name "Net-(U8-QD)") (class "Default")
      (node (ref "R55") (pin "2") (pinfunction "2_2") (pintype "passive"))
      (node (ref "U8") (pin "3") (pinfunction "QD_3") (pintype "tri_state"))
    )
    (net (code "142") (name "Net-(U8-QE)") (class "Default")
      (node (ref "R57") (pin "2") (pinfunction "2_2") (pintype "passive"))
      (node (ref "U8") (pin "4") (pinfunction "QE_4") (pintype "tri_state"))
    )
    (net (code "143") (name "Net-(U8-QF)") (class "Default")
      (node (ref "R59") (pin "2") (pinfunction "2_2") (pintype "passive"))
      (node (ref "U8") (pin "5") (pinfunction "QF_5") (pintype "tri_state"))
    )
    (net (code "144") (name "Net-(U8-QG)") (class "Default")
      (node (ref "R61") (pin "2") (pinfunction "2_2") (pintype "passive"))
      (node (ref "U8") (pin "6") (pinfunction "QG_6") (pintype "tri_state"))
    )
    (net (code "145") (name "Net-(U8-QH)") (class "Default")
      (node (ref "R63") (pin "2") (pinfunction "2_2") (pintype "passive"))
      (node (ref "U8") (pin "7") (pinfunction "QH_7") (pintype "tri_state"))
    )
    (net (code "146") (name "Net-(U10-QA)") (class "Default")
      (node (ref "R52") (pin "2") (pinfunction "2_2") (pintype "passive"))
      (node (ref "U10") (pin "15") (pinfunction "QA_15") (pintype "tri_state"))
    )
    (net (code "147") (name "Net-(U10-QB)") (class "Default")
      (node (ref "R54") (pin "2") (pinfunction "2_2") (pintype "passive"))
      (node (ref "U10") (pin "1") (pinfunction "QB_1") (pintype "tri_state"))
    )
    (net (code "148") (name "Net-(U10-QC)") (class "Default")
      (node (ref "R56") (pin "2") (pinfunction "2_2") (pintype "passive"))
      (node (ref "U10") (pin "2") (pinfunction "QC_2") (pintype "tri_state"))
    )
    (net (code "149") (name "Net-(U10-QD)") (class "Default")
      (node (ref "R58") (pin "2") (pinfunction "2_2") (pintype "passive"))
      (node (ref "U10") (pin "3") (pinfunction "QD_3") (pintype "tri_state"))
    )
    (net (code "150") (name "Net-(U10-QE)") (class "Default")
      (node (ref "R60") (pin "2") (pinfunction "2_2") (pintype "passive"))
      (node (ref "U10") (pin "4") (pinfunction "QE_4") (pintype "tri_state"))
    )
    (net (code "151") (name "Net-(U10-QF)") (class "Default")
      (node (ref "R62") (pin "2") (pinfunction "2_2") (pintype "passive"))
      (node (ref "U10") (pin "5") (pinfunction "QF_5") (pintype "tri_state"))
    )
    (net (code "152") (name "Net-(U10-QG)") (class "Default")
      (node (ref "R64") (pin "2") (pinfunction "2_2") (pintype "passive"))
      (node (ref "U10") (pin "6") (pinfunction "QG_6") (pintype "tri_state"))
    )
    (net (code "153") (name "Net-(U10-QH)") (class "Default")
      (node (ref "R65") (pin "2") (pinfunction "2_2") (pintype "passive"))
      (node (ref "U10") (pin "7") (pinfunction "QH_7") (pintype "tri_state"))
    )
    (net (code "154") (name "unconnected-(U1-D2-Pad4)") (class "Default")
      (node (ref "U1") (pin "4") (pinfunction "D2_4") (pintype "bidirectional"))
    )
    (net (code "155") (name "unconnected-(U1-D4-Pad5)") (class "Default")
      (node (ref "U1") (pin "5") (pinfunction "D4_5") (pintype "bidirectional"))
    )
    (net (code "156") (name "unconnected-(U1-D5-Pad8)") (class "Default")
      (node (ref "U1") (pin "8") (pinfunction "D5_8") (pintype "bidirectional"))
    )
    (net (code "157") (name "unconnected-(U1-D12-Pad27)") (class "Default")
      (node (ref "U1") (pin "27") (pinfunction "D12_27") (pintype "bidirectional"))
    )
    (net (code "158") (name "unconnected-(U1-D13-Pad28)") (class "Default")
      (node (ref "U1") (pin "28") (pinfunction "D13_28") (pintype "bidirectional"))
    )
    (net (code "159") (name "unconnected-(U1-D14-Pad26)") (class "Default")
      (node (ref "U1") (pin "26") (pinfunction "D14_26") (pintype "bidirectional"))
    )
    (net (code "160") (name "unconnected-(U1-D15-Pad3)") (class "Default")
      (node (ref "U1") (pin "3") (pinfunction "D15_3") (pintype "bidirectional"))
    )
    (net (code "161") (name "unconnected-(U1-D19-Pad10)") (class "Default")
      (node (ref "U1") (pin "10") (pinfunction "D19_10") (pintype "bidirectional"))
    )
    (net (code "162") (name "unconnected-(U1-D21-Pad11)") (class "Default")
      (node (ref "U1") (pin "11") (pinfunction "D21_11") (pintype "bidirectional"))
    )
    (net (code "163") (name "unconnected-(U1-D22-Pad14)") (class "Default")
      (node (ref "U1") (pin "14") (pinfunction "D22_14") (pintype "bidirectional"))
    )
    (net (code "164") (name "unconnected-(U1-D23-Pad15)") (class "Default")
      (node (ref "U1") (pin "15") (pinfunction "D23_15") (pintype "bidirectional"))
    )
    (net (code "165") (name "unconnected-(U1-D25-Pad23)") (class "Default")
      (node (ref "U1") (pin "23") (pinfunction "D25_23") (pintype "bidirectional"))
    )
    (net (code "166") (name "unconnected-(U1-D26-Pad24)") (class "Default")
      (node (ref "U1") (pin "24") (pinfunction "D26_24") (pintype "bidirectional"))
    )
    (net (code "167") (name "unconnected-(U1-D27-Pad25)") (class "Default")
      (node (ref "U1") (pin "25") (pinfunction "D27_25") (pintype "bidirectional"))
    )
    (net (code "168") (name "unconnected-(U1-D32-Pad21)") (class "Default")
      (node (ref "U1") (pin "21") (pinfunction "D32_21") (pintype "bidirectional"))
    )
    (net (code "169") (name "unconnected-(U1-D33-Pad22)") (class "Default")
      (node (ref "U1") (pin "22") (pinfunction "D33_22") (pintype "bidirectional"))
    )
    (net (code "170") (name "unconnected-(U1-D34-Pad19)") (class "Default")
      (node (ref "U1") (pin "19") (pinfunction "D34_19") (pintype "bidirectional"))
    )
    (net (code "171") (name "unconnected-(U1-D35-Pad20)") (class "Default")
      (node (ref "U1") (pin "20") (pinfunction "D35_20") (pintype "bidirectional"))
    )
    (net (code "172") (name "unconnected-(U1-EN-Pad16)") (class "Default")
      (node (ref "U1") (pin "16") (pinfunction "EN_16") (pintype "input"))
    )
    (net (code "173") (name "unconnected-(U1-RX0-Pad12)") (class "Default")
      (node (ref "U1") (pin "12") (pinfunction "RX0_12") (pintype "input"))
    )
    (net (code "174") (name "unconnected-(U1-TX0-Pad13)") (class "Default")
      (node (ref "U1") (pin "13") (pinfunction "TX0_13") (pintype "output"))
    )
    (net (code "175") (name "unconnected-(U1-VN-Pad18)") (class "Default")
      (node (ref "U1") (pin "18") (pinfunction "VN_18") (pintype "bidirectional"))
    )
    (net (code "176") (name "unconnected-(U1-VP-Pad17)") (class "Default")
      (node (ref "U1") (pin "17") (pinfunction "VP_17") (pintype "bidirectional"))
    )
    (net (code "177") (name "unconnected-(U9-SDO-Pad9)") (class "Default")
      (node (ref "U9") (pin "9") (pinfunction "SDO_9") (pintype "output"))
    )
  )
)
